# HDMI_To_MIPI_PHY.net
KiCad netlist of a schematic drawn in Altium Designer
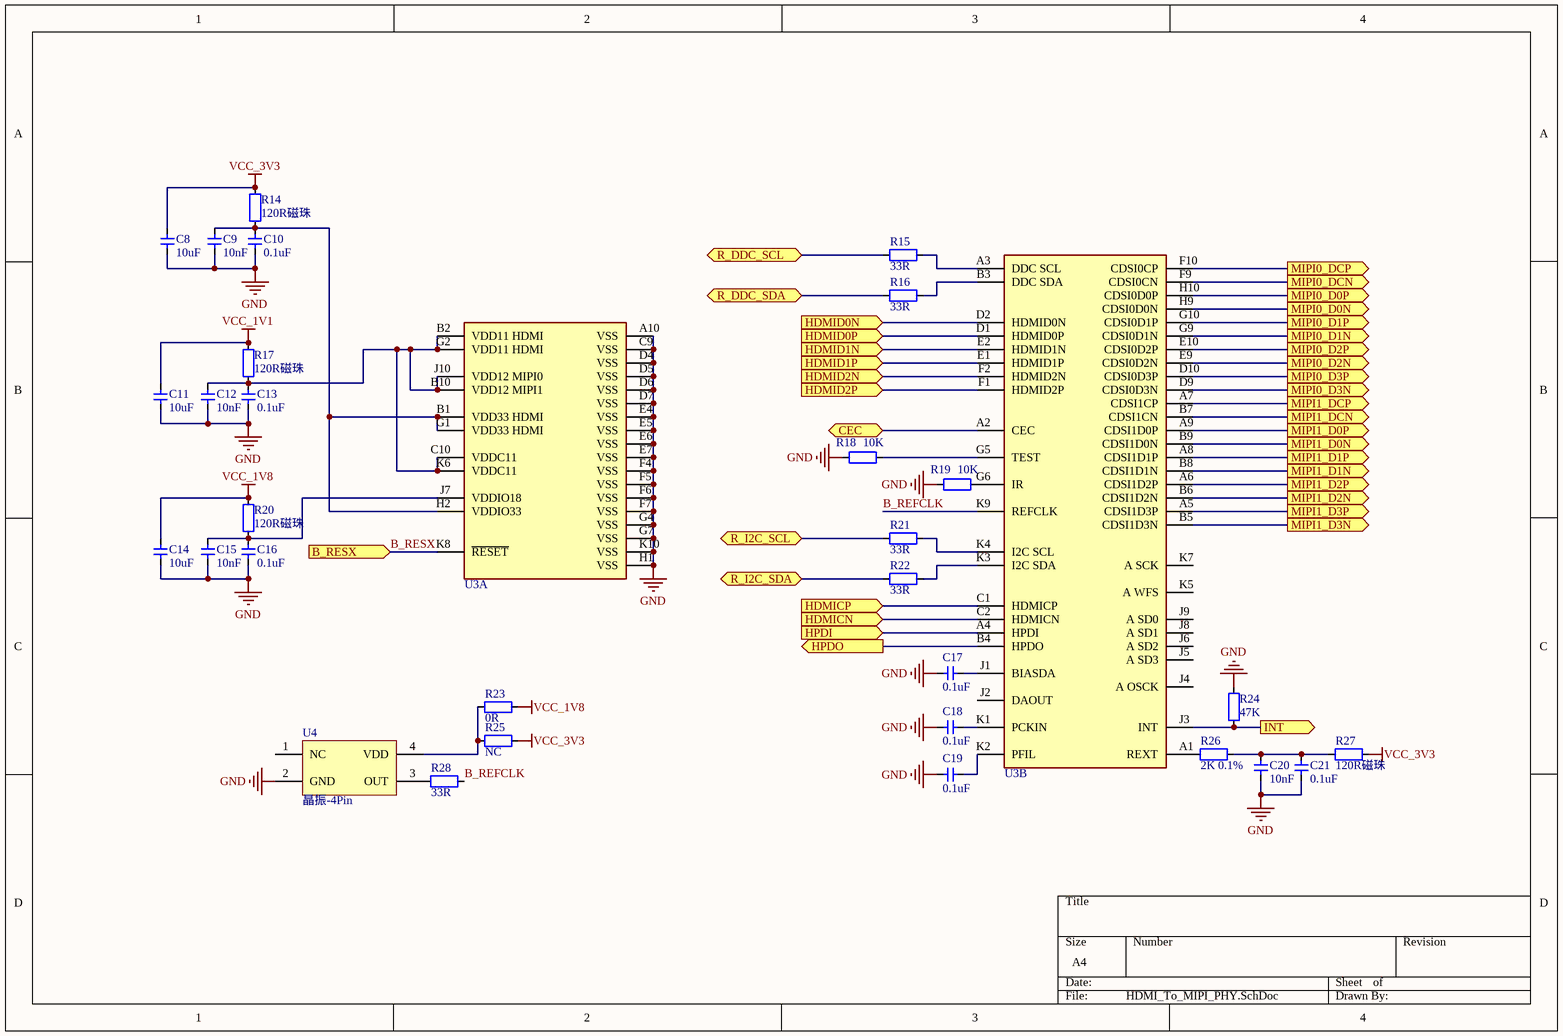
[diagram p0: HDMI_To_MIPI_PHY.SchDoc]

(export (version "E")
  (design (tool "Eeschema 10.0.6"))
  (components
    (comp (ref "C8")
      (value "10uF")
      (footprint "CAP_0402")
      (description "Capacitor")
      (libsource (lib "MyPcbLib") (part "电容-0402"))
    )
    (comp (ref "C9")
      (value "10nF")
      (footprint "CAP_0402")
      (description "Capacitor")
      (libsource (lib "MyPcbLib") (part "电容-0402"))
    )
    (comp (ref "C10")
      (value "0.1uF")
      (footprint "CAP_0402")
      (description "Capacitor")
      (libsource (lib "MyPcbLib") (part "电容-0402"))
    )
    (comp (ref "C11")
      (value "10uF")
      (footprint "CAP_0402")
      (description "Capacitor")
      (libsource (lib "MyPcbLib") (part "电容-0402"))
    )
    (comp (ref "C12")
      (value "10nF")
      (footprint "CAP_0402")
      (description "Capacitor")
      (libsource (lib "MyPcbLib") (part "电容-0402"))
    )
    (comp (ref "C13")
      (value "0.1uF")
      (footprint "CAP_0402")
      (description "Capacitor")
      (libsource (lib "MyPcbLib") (part "电容-0402"))
    )
    (comp (ref "C14")
      (value "10uF")
      (footprint "CAP_0402")
      (description "Capacitor")
      (libsource (lib "MyPcbLib") (part "电容-0402"))
    )
    (comp (ref "C15")
      (value "10nF")
      (footprint "CAP_0402")
      (description "Capacitor")
      (libsource (lib "MyPcbLib") (part "电容-0402"))
    )
    (comp (ref "C16")
      (value "0.1uF")
      (footprint "CAP_0402")
      (description "Capacitor")
      (libsource (lib "MyPcbLib") (part "电容-0402"))
    )
    (comp (ref "C17")
      (value "0.1uF")
      (footprint "CAP_0402")
      (description "Capacitor")
      (libsource (lib "MyPcbLib") (part "电容-0402"))
    )
    (comp (ref "C18")
      (value "0.1uF")
      (footprint "CAP_0402")
      (description "Capacitor")
      (libsource (lib "MyPcbLib") (part "电容-0402"))
    )
    (comp (ref "C19")
      (value "0.1uF")
      (footprint "CAP_0402")
      (description "Capacitor")
      (libsource (lib "MyPcbLib") (part "电容-0402"))
    )
    (comp (ref "C20")
      (value "10nF")
      (footprint "CAP_0402")
      (description "Capacitor")
      (libsource (lib "MyPcbLib") (part "电容-0402"))
    )
    (comp (ref "C21")
      (value "0.1uF")
      (footprint "CAP_0402")
      (description "Capacitor")
      (libsource (lib "MyPcbLib") (part "电容-0402"))
    )
    (comp (ref "R14")
      (value "120R磁珠")
      (footprint "0805-L")
      (description "Resistor")
      (libsource (lib "MyPcbLib") (part "电阻-0805"))
    )
    (comp (ref "R15")
      (value "33R")
      (footprint "RES_0402")
      (description "Resistor")
      (libsource (lib "MyPcbLib") (part "电阻-0402"))
    )
    (comp (ref "R16")
      (value "33R")
      (footprint "RES_0402")
      (description "Resistor")
      (libsource (lib "MyPcbLib") (part "电阻-0402"))
    )
    (comp (ref "R17")
      (value "120R磁珠")
      (footprint "0805-L")
      (description "Resistor")
      (libsource (lib "MyPcbLib") (part "电阻-0805"))
    )
    (comp (ref "R18")
      (value "10K")
      (footprint "RES_0402")
      (description "Resistor")
      (libsource (lib "MyPcbLib") (part "电阻-0402"))
    )
    (comp (ref "R19")
      (value "10K")
      (footprint "RES_0402")
      (description "Resistor")
      (libsource (lib "MyPcbLib") (part "电阻-0402"))
    )
    (comp (ref "R20")
      (value "120R磁珠")
      (footprint "0805-L")
      (description "Resistor")
      (libsource (lib "MyPcbLib") (part "电阻-0805"))
    )
    (comp (ref "R21")
      (value "33R")
      (footprint "RES_0402")
      (description "Resistor")
      (libsource (lib "MyPcbLib") (part "电阻-0402"))
    )
    (comp (ref "R22")
      (value "33R")
      (footprint "RES_0402")
      (description "Resistor")
      (libsource (lib "MyPcbLib") (part "电阻-0402"))
    )
    (comp (ref "R23")
      (value "0R")
      (footprint "RES_0402")
      (description "Resistor")
      (libsource (lib "MyPcbLib") (part "电阻-0402"))
    )
    (comp (ref "R24")
      (value "47K")
      (footprint "RES_0402")
      (description "Resistor")
      (libsource (lib "") (part "电阻-0402_1"))
    )
    (comp (ref "R25")
      (value "NC")
      (footprint "RES_0402")
      (description "Resistor")
      (libsource (lib "MyPcbLib") (part "电阻-0402"))
    )
    (comp (ref "R26")
      (value "2K 0.1%")
      (footprint "RES_0402")
      (description "Resistor")
      (libsource (lib "MyPcbLib") (part "电阻-0402"))
    )
    (comp (ref "R27")
      (value "120R磁珠")
      (footprint "0805-L")
      (description "Resistor")
      (libsource (lib "") (part "电阻-0805_1"))
    )
    (comp (ref "R28")
      (value "33R")
      (footprint "RES_0402")
      (description "Resistor")
      (libsource (lib "MyPcbLib") (part "电阻-0402"))
    )
    (comp (ref "U3")
      (value "TC358870XBG")
      (footprint "VFBGA-80")
      (libsource (lib "mLib") (part "TC358870XBG"))
    )
    (comp (ref "U4")
      (value "晶振-4Pin")
      (footprint "晶振2520")
      (description "5032 有源")
      (libsource (lib "mLib") (part "晶振-4Pin"))
    )
  )
  (nets
    (net (code "1") (name "/B_REFCLK") (class "Default")
      (node (ref "R28") (pin "2") (pinfunction "2_2") (pintype "passive"))
      (node (ref "U3") (pin "K9") (pinfunction "REFCLK_K9") (pintype "passive"))
    )
    (net (code "2") (name "/B_RESX") (class "Default")
      (node (ref "U3") (pin "K8") (pinfunction "~{RESET}_K8") (pintype "passive"))
    )
    (net (code "3") (name "/CEC") (class "Default")
      (node (ref "U3") (pin "A2") (pinfunction "CEC_A2") (pintype "passive"))
    )
    (net (code "4") (name "/HDMICN") (class "Default")
      (node (ref "U3") (pin "C2") (pinfunction "HDMICN_C2") (pintype "passive"))
    )
    (net (code "5") (name "/HDMICP") (class "Default")
      (node (ref "U3") (pin "C1") (pinfunction "HDMICP_C1") (pintype "passive"))
    )
    (net (code "6") (name "/HDMID0N") (class "Default")
      (node (ref "U3") (pin "D2") (pinfunction "HDMID0N_D2") (pintype "passive"))
    )
    (net (code "7") (name "/HDMID0P") (class "Default")
      (node (ref "U3") (pin "D1") (pinfunction "HDMID0P_D1") (pintype "passive"))
    )
    (net (code "8") (name "/HDMID1N") (class "Default")
      (node (ref "U3") (pin "E2") (pinfunction "HDMID1N_E2") (pintype "passive"))
    )
    (net (code "9") (name "/HDMID1P") (class "Default")
      (node (ref "U3") (pin "E1") (pinfunction "HDMID1P_E1") (pintype "passive"))
    )
    (net (code "10") (name "/HDMID2N") (class "Default")
      (node (ref "U3") (pin "F2") (pinfunction "HDMID2N_F2") (pintype "passive"))
    )
    (net (code "11") (name "/HDMID2P") (class "Default")
      (node (ref "U3") (pin "F1") (pinfunction "HDMID2P_F1") (pintype "passive"))
    )
    (net (code "12") (name "/HPDI") (class "Default")
      (node (ref "U3") (pin "A4") (pinfunction "HPDI_A4") (pintype "passive"))
    )
    (net (code "13") (name "/HPDO") (class "Default")
      (node (ref "U3") (pin "B4") (pinfunction "HPDO_B4") (pintype "passive"))
    )
    (net (code "14") (name "/INT") (class "Default")
      (node (ref "R24") (pin "1") (pinfunction "1_1") (pintype "passive"))
      (node (ref "U3") (pin "J3") (pinfunction "INT_J3") (pintype "passive"))
    )
    (net (code "15") (name "/MIPI0_D0N") (class "Default")
      (node (ref "U3") (pin "H9") (pinfunction "CDSI0D0N_H9") (pintype "passive"))
    )
    (net (code "16") (name "/MIPI0_D0P") (class "Default")
      (node (ref "U3") (pin "H10") (pinfunction "CDSI0D0P_H10") (pintype "passive"))
    )
    (net (code "17") (name "/MIPI0_D1N") (class "Default")
      (node (ref "U3") (pin "G9") (pinfunction "CDSI0D1N_G9") (pintype "passive"))
    )
    (net (code "18") (name "/MIPI0_D1P") (class "Default")
      (node (ref "U3") (pin "G10") (pinfunction "CDSI0D1P_G10") (pintype "passive"))
    )
    (net (code "19") (name "/MIPI0_D2N") (class "Default")
      (node (ref "U3") (pin "E9") (pinfunction "CDSI0D2N_E9") (pintype "passive"))
    )
    (net (code "20") (name "/MIPI0_D2P") (class "Default")
      (node (ref "U3") (pin "E10") (pinfunction "CDSI0D2P_E10") (pintype "passive"))
    )
    (net (code "21") (name "/MIPI0_D3N") (class "Default")
      (node (ref "U3") (pin "D9") (pinfunction "CDSI0D3N_D9") (pintype "passive"))
    )
    (net (code "22") (name "/MIPI0_D3P") (class "Default")
      (node (ref "U3") (pin "D10") (pinfunction "CDSI0D3P_D10") (pintype "passive"))
    )
    (net (code "23") (name "/MIPI0_DCN") (class "Default")
      (node (ref "U3") (pin "F9") (pinfunction "CDSI0CN_F9") (pintype "passive"))
    )
    (net (code "24") (name "/MIPI0_DCP") (class "Default")
      (node (ref "U3") (pin "F10") (pinfunction "CDSI0CP_F10") (pintype "passive"))
    )
    (net (code "25") (name "/MIPI1_D0N") (class "Default")
      (node (ref "U3") (pin "B9") (pinfunction "CDSI1D0N_B9") (pintype "passive"))
    )
    (net (code "26") (name "/MIPI1_D0P") (class "Default")
      (node (ref "U3") (pin "A9") (pinfunction "CDSI1D0P_A9") (pintype "passive"))
    )
    (net (code "27") (name "/MIPI1_D1N") (class "Default")
      (node (ref "U3") (pin "B8") (pinfunction "CDSI1D1N_B8") (pintype "passive"))
    )
    (net (code "28") (name "/MIPI1_D1P") (class "Default")
      (node (ref "U3") (pin "A8") (pinfunction "CDSI1D1P_A8") (pintype "passive"))
    )
    (net (code "29") (name "/MIPI1_D2N") (class "Default")
      (node (ref "U3") (pin "B6") (pinfunction "CDSI1D2N_B6") (pintype "passive"))
    )
    (net (code "30") (name "/MIPI1_D2P") (class "Default")
      (node (ref "U3") (pin "A6") (pinfunction "CDSI1D2P_A6") (pintype "passive"))
    )
    (net (code "31") (name "/MIPI1_D3N") (class "Default")
      (node (ref "U3") (pin "B5") (pinfunction "CDSI1D3N_B5") (pintype "passive"))
    )
    (net (code "32") (name "/MIPI1_D3P") (class "Default")
      (node (ref "U3") (pin "A5") (pinfunction "CDSI1D3P_A5") (pintype "passive"))
    )
    (net (code "33") (name "/MIPI1_DCN") (class "Default")
      (node (ref "U3") (pin "B7") (pinfunction "CDSI1CN_B7") (pintype "passive"))
    )
    (net (code "34") (name "/MIPI1_DCP") (class "Default")
      (node (ref "U3") (pin "A7") (pinfunction "CDSI1CP_A7") (pintype "passive"))
    )
    (net (code "35") (name "/R_DDC_SCL") (class "Default")
      (node (ref "R15") (pin "1") (pinfunction "1_1") (pintype "passive"))
    )
    (net (code "36") (name "/R_DDC_SDA") (class "Default")
      (node (ref "R16") (pin "1") (pinfunction "1_1") (pintype "passive"))
    )
    (net (code "37") (name "/R_I2C_SCL") (class "Default")
      (node (ref "R21") (pin "1") (pinfunction "1_1") (pintype "passive"))
    )
    (net (code "38") (name "/R_I2C_SDA") (class "Default")
      (node (ref "R22") (pin "1") (pinfunction "1_1") (pintype "passive"))
    )
    (net (code "39") (name "GND") (class "Default")
      (node (ref "C10") (pin "1") (pinfunction "1_1") (pintype "passive"))
      (node (ref "C11") (pin "1") (pinfunction "1_1") (pintype "passive"))
      (node (ref "C12") (pin "1") (pinfunction "1_1") (pintype "passive"))
      (node (ref "C13") (pin "1") (pinfunction "1_1") (pintype "passive"))
      (node (ref "C14") (pin "1") (pinfunction "1_1") (pintype "passive"))
      (node (ref "C15") (pin "1") (pinfunction "1_1") (pintype "passive"))
      (node (ref "C16") (pin "1") (pinfunction "1_1") (pintype "passive"))
      (node (ref "C17") (pin "2") (pinfunction "2_2") (pintype "passive"))
      (node (ref "C18") (pin "2") (pinfunction "2_2") (pintype "passive"))
      (node (ref "C19") (pin "2") (pinfunction "2_2") (pintype "passive"))
      (node (ref "C20") (pin "1") (pinfunction "1_1") (pintype "passive"))
      (node (ref "C21") (pin "1") (pinfunction "1_1") (pintype "passive"))
      (node (ref "C8") (pin "1") (pinfunction "1_1") (pintype "passive"))
      (node (ref "C9") (pin "1") (pinfunction "1_1") (pintype "passive"))
      (node (ref "R18") (pin "1") (pinfunction "1_1") (pintype "passive"))
      (node (ref "R19") (pin "1") (pinfunction "1_1") (pintype "passive"))
      (node (ref "R24") (pin "2") (pinfunction "2_2") (pintype "passive"))
      (node (ref "U3") (pin "A10") (pinfunction "VSS_A10") (pintype "passive"))
      (node (ref "U3") (pin "C9") (pinfunction "VSS_C9") (pintype "passive"))
      (node (ref "U3") (pin "D4") (pinfunction "VSS_D4") (pintype "passive"))
      (node (ref "U3") (pin "D5") (pinfunction "VSS_D5") (pintype "passive"))
      (node (ref "U3") (pin "D6") (pinfunction "VSS_D6") (pintype "passive"))
      (node (ref "U3") (pin "D7") (pinfunction "VSS_D7") (pintype "passive"))
      (node (ref "U3") (pin "E4") (pinfunction "VSS_E4") (pintype "passive"))
      (node (ref "U3") (pin "E5") (pinfunction "VSS_E5") (pintype "passive"))
      (node (ref "U3") (pin "E6") (pinfunction "VSS_E6") (pintype "passive"))
      (node (ref "U3") (pin "E7") (pinfunction "VSS_E7") (pintype "passive"))
      (node (ref "U3") (pin "F4") (pinfunction "VSS_F4") (pintype "passive"))
      (node (ref "U3") (pin "F5") (pinfunction "VSS_F5") (pintype "passive"))
      (node (ref "U3") (pin "F6") (pinfunction "VSS_F6") (pintype "passive"))
      (node (ref "U3") (pin "F7") (pinfunction "VSS_F7") (pintype "passive"))
      (node (ref "U3") (pin "G4") (pinfunction "VSS_G4") (pintype "passive"))
      (node (ref "U3") (pin "G7") (pinfunction "VSS_G7") (pintype "passive"))
      (node (ref "U3") (pin "H1") (pinfunction "VSS_H1") (pintype "passive"))
      (node (ref "U3") (pin "K10") (pinfunction "VSS_K10") (pintype "passive"))
      (node (ref "U4") (pin "2") (pinfunction "GND_2") (pintype "passive"))
    )
    (net (code "40") (name "Net-(C20-Pad2)") (class "Default")
      (node (ref "C20") (pin "2") (pinfunction "2_2") (pintype "passive"))
      (node (ref "C21") (pin "2") (pinfunction "2_2") (pintype "passive"))
      (node (ref "R26") (pin "2") (pinfunction "2_2") (pintype "passive"))
      (node (ref "R27") (pin "1") (pinfunction "1_1") (pintype "passive"))
    )
    (net (code "41") (name "Net-(U3A-VDD12_MIPI0)") (class "Default")
      (node (ref "C12") (pin "2") (pinfunction "2_2") (pintype "passive"))
      (node (ref "C13") (pin "2") (pinfunction "2_2") (pintype "passive"))
      (node (ref "R17") (pin "1") (pinfunction "1_1") (pintype "passive"))
      (node (ref "U3") (pin "B10") (pinfunction "VDD12_MIPI1_B10") (pintype "passive"))
      (node (ref "U3") (pin "B2") (pinfunction "VDD11_HDMI_B2") (pintype "passive"))
      (node (ref "U3") (pin "C10") (pinfunction "VDDC11_C10") (pintype "passive"))
      (node (ref "U3") (pin "G2") (pinfunction "VDD11_HDMI_G2") (pintype "passive"))
      (node (ref "U3") (pin "J10") (pinfunction "VDD12_MIPI0_J10") (pintype "passive"))
      (node (ref "U3") (pin "K6") (pinfunction "VDDC11_K6") (pintype "passive"))
    )
    (net (code "42") (name "Net-(U3A-VDDIO18)") (class "Default")
      (node (ref "C15") (pin "2") (pinfunction "2_2") (pintype "passive"))
      (node (ref "C16") (pin "2") (pinfunction "2_2") (pintype "passive"))
      (node (ref "R20") (pin "1") (pinfunction "1_1") (pintype "passive"))
      (node (ref "U3") (pin "J7") (pinfunction "VDDIO18_J7") (pintype "passive"))
    )
    (net (code "43") (name "Net-(U3A-VDDIO33)") (class "Default")
      (node (ref "C10") (pin "2") (pinfunction "2_2") (pintype "passive"))
      (node (ref "C9") (pin "2") (pinfunction "2_2") (pintype "passive"))
      (node (ref "R14") (pin "1") (pinfunction "1_1") (pintype "passive"))
      (node (ref "U3") (pin "B1") (pinfunction "VDD33_HDMI_B1") (pintype "passive"))
      (node (ref "U3") (pin "G1") (pinfunction "VDD33_HDMI_G1") (pintype "passive"))
      (node (ref "U3") (pin "H2") (pinfunction "VDDIO33_H2") (pintype "passive"))
    )
    (net (code "44") (name "Net-(U3B-BIASDA)") (class "Default")
      (node (ref "C17") (pin "1") (pinfunction "1_1") (pintype "passive"))
      (node (ref "U3") (pin "J1") (pinfunction "BIASDA_J1") (pintype "passive"))
    )
    (net (code "45") (name "Net-(U3B-DDC_SCL)") (class "Default")
      (node (ref "R15") (pin "2") (pinfunction "2_2") (pintype "passive"))
      (node (ref "U3") (pin "A3") (pinfunction "DDC_SCL_A3") (pintype "passive"))
    )
    (net (code "46") (name "Net-(U3B-DDC_SDA)") (class "Default")
      (node (ref "R16") (pin "2") (pinfunction "2_2") (pintype "passive"))
      (node (ref "U3") (pin "B3") (pinfunction "DDC_SDA_B3") (pintype "passive"))
    )
    (net (code "47") (name "Net-(U3B-I2C_SCL)") (class "Default")
      (node (ref "R21") (pin "2") (pinfunction "2_2") (pintype "passive"))
      (node (ref "U3") (pin "K4") (pinfunction "I2C_SCL_K4") (pintype "passive"))
    )
    (net (code "48") (name "Net-(U3B-I2C_SDA)") (class "Default")
      (node (ref "R22") (pin "2") (pinfunction "2_2") (pintype "passive"))
      (node (ref "U3") (pin "K3") (pinfunction "I2C_SDA_K3") (pintype "passive"))
    )
    (net (code "49") (name "Net-(U3B-IR)") (class "Default")
      (node (ref "R19") (pin "2") (pinfunction "2_2") (pintype "passive"))
      (node (ref "U3") (pin "G6") (pinfunction "IR_G6") (pintype "passive"))
    )
    (net (code "50") (name "Net-(U3B-PCKIN)") (class "Default")
      (node (ref "C18") (pin "1") (pinfunction "1_1") (pintype "passive"))
      (node (ref "U3") (pin "K1") (pinfunction "PCKIN_K1") (pintype "passive"))
    )
    (net (code "51") (name "Net-(U3B-PFIL)") (class "Default")
      (node (ref "C19") (pin "1") (pinfunction "1_1") (pintype "passive"))
      (node (ref "U3") (pin "K2") (pinfunction "PFIL_K2") (pintype "passive"))
    )
    (net (code "52") (name "Net-(U3B-REXT)") (class "Default")
      (node (ref "R26") (pin "1") (pinfunction "1_1") (pintype "passive"))
      (node (ref "U3") (pin "A1") (pinfunction "REXT_A1") (pintype "passive"))
    )
    (net (code "53") (name "Net-(U3B-TEST)") (class "Default")
      (node (ref "R18") (pin "2") (pinfunction "2_2") (pintype "passive"))
      (node (ref "U3") (pin "G5") (pinfunction "TEST_G5") (pintype "passive"))
    )
    (net (code "54") (name "Net-(U4-OUT)") (class "Default")
      (node (ref "R28") (pin "1") (pinfunction "1_1") (pintype "passive"))
      (node (ref "U4") (pin "3") (pinfunction "OUT_3") (pintype "passive"))
    )
    (net (code "55") (name "Net-(U4-VDD)") (class "Default")
      (node (ref "R23") (pin "1") (pinfunction "1_1") (pintype "passive"))
      (node (ref "R25") (pin "1") (pinfunction "1_1") (pintype "passive"))
      (node (ref "U4") (pin "4") (pinfunction "VDD_4") (pintype "passive"))
    )
    (net (code "56") (name "VCC_1V1") (class "Default")
      (node (ref "C11") (pin "2") (pinfunction "2_2") (pintype "passive"))
      (node (ref "R17") (pin "2") (pinfunction "2_2") (pintype "passive"))
    )
    (net (code "57") (name "VCC_1V8") (class "Default")
      (node (ref "C14") (pin "2") (pinfunction "2_2") (pintype "passive"))
      (node (ref "R20") (pin "2") (pinfunction "2_2") (pintype "passive"))
      (node (ref "R23") (pin "2") (pinfunction "2_2") (pintype "passive"))
    )
    (net (code "58") (name "VCC_3V3") (class "Default")
      (node (ref "C8") (pin "2") (pinfunction "2_2") (pintype "passive"))
      (node (ref "R14") (pin "2") (pinfunction "2_2") (pintype "passive"))
      (node (ref "R25") (pin "2") (pinfunction "2_2") (pintype "passive"))
      (node (ref "R27") (pin "2") (pinfunction "2_2") (pintype "passive"))
    )
    (net (code "59") (name "unconnected-(U3B-A_OSCK-PadJ4)") (class "Default")
      (node (ref "U3") (pin "J4") (pinfunction "A_OSCK_J4") (pintype "passive"))
    )
    (net (code "60") (name "unconnected-(U3B-A_SCK-PadK7)") (class "Default")
      (node (ref "U3") (pin "K7") (pinfunction "A_SCK_K7") (pintype "passive"))
    )
    (net (code "61") (name "unconnected-(U3B-A_SD0-PadJ9)") (class "Default")
      (node (ref "U3") (pin "J9") (pinfunction "A_SD0_J9") (pintype "passive"))
    )
    (net (code "62") (name "unconnected-(U3B-A_SD1-PadJ8)") (class "Default")
      (node (ref "U3") (pin "J8") (pinfunction "A_SD1_J8") (pintype "passive"))
    )
    (net (code "63") (name "unconnected-(U3B-A_SD2-PadJ6)") (class "Default")
      (node (ref "U3") (pin "J6") (pinfunction "A_SD2_J6") (pintype "passive"))
    )
    (net (code "64") (name "unconnected-(U3B-A_SD3-PadJ5)") (class "Default")
      (node (ref "U3") (pin "J5") (pinfunction "A_SD3_J5") (pintype "passive"))
    )
    (net (code "65") (name "unconnected-(U3B-A_WFS-PadK5)") (class "Default")
      (node (ref "U3") (pin "K5") (pinfunction "A_WFS_K5") (pintype "passive"))
    )
    (net (code "66") (name "unconnected-(U3B-DAOUT-PadJ2)") (class "Default")
      (node (ref "U3") (pin "J2") (pinfunction "DAOUT_J2") (pintype "passive"))
    )
    (net (code "67") (name "unconnected-(U4-NC-Pad1)") (class "Default")
      (node (ref "U4") (pin "1") (pinfunction "NC_1") (pintype "passive"))
    )
  )
)
